# BBB_I2S_CAPE.net
KiCad netlist of a schematic drawn in EAGLE
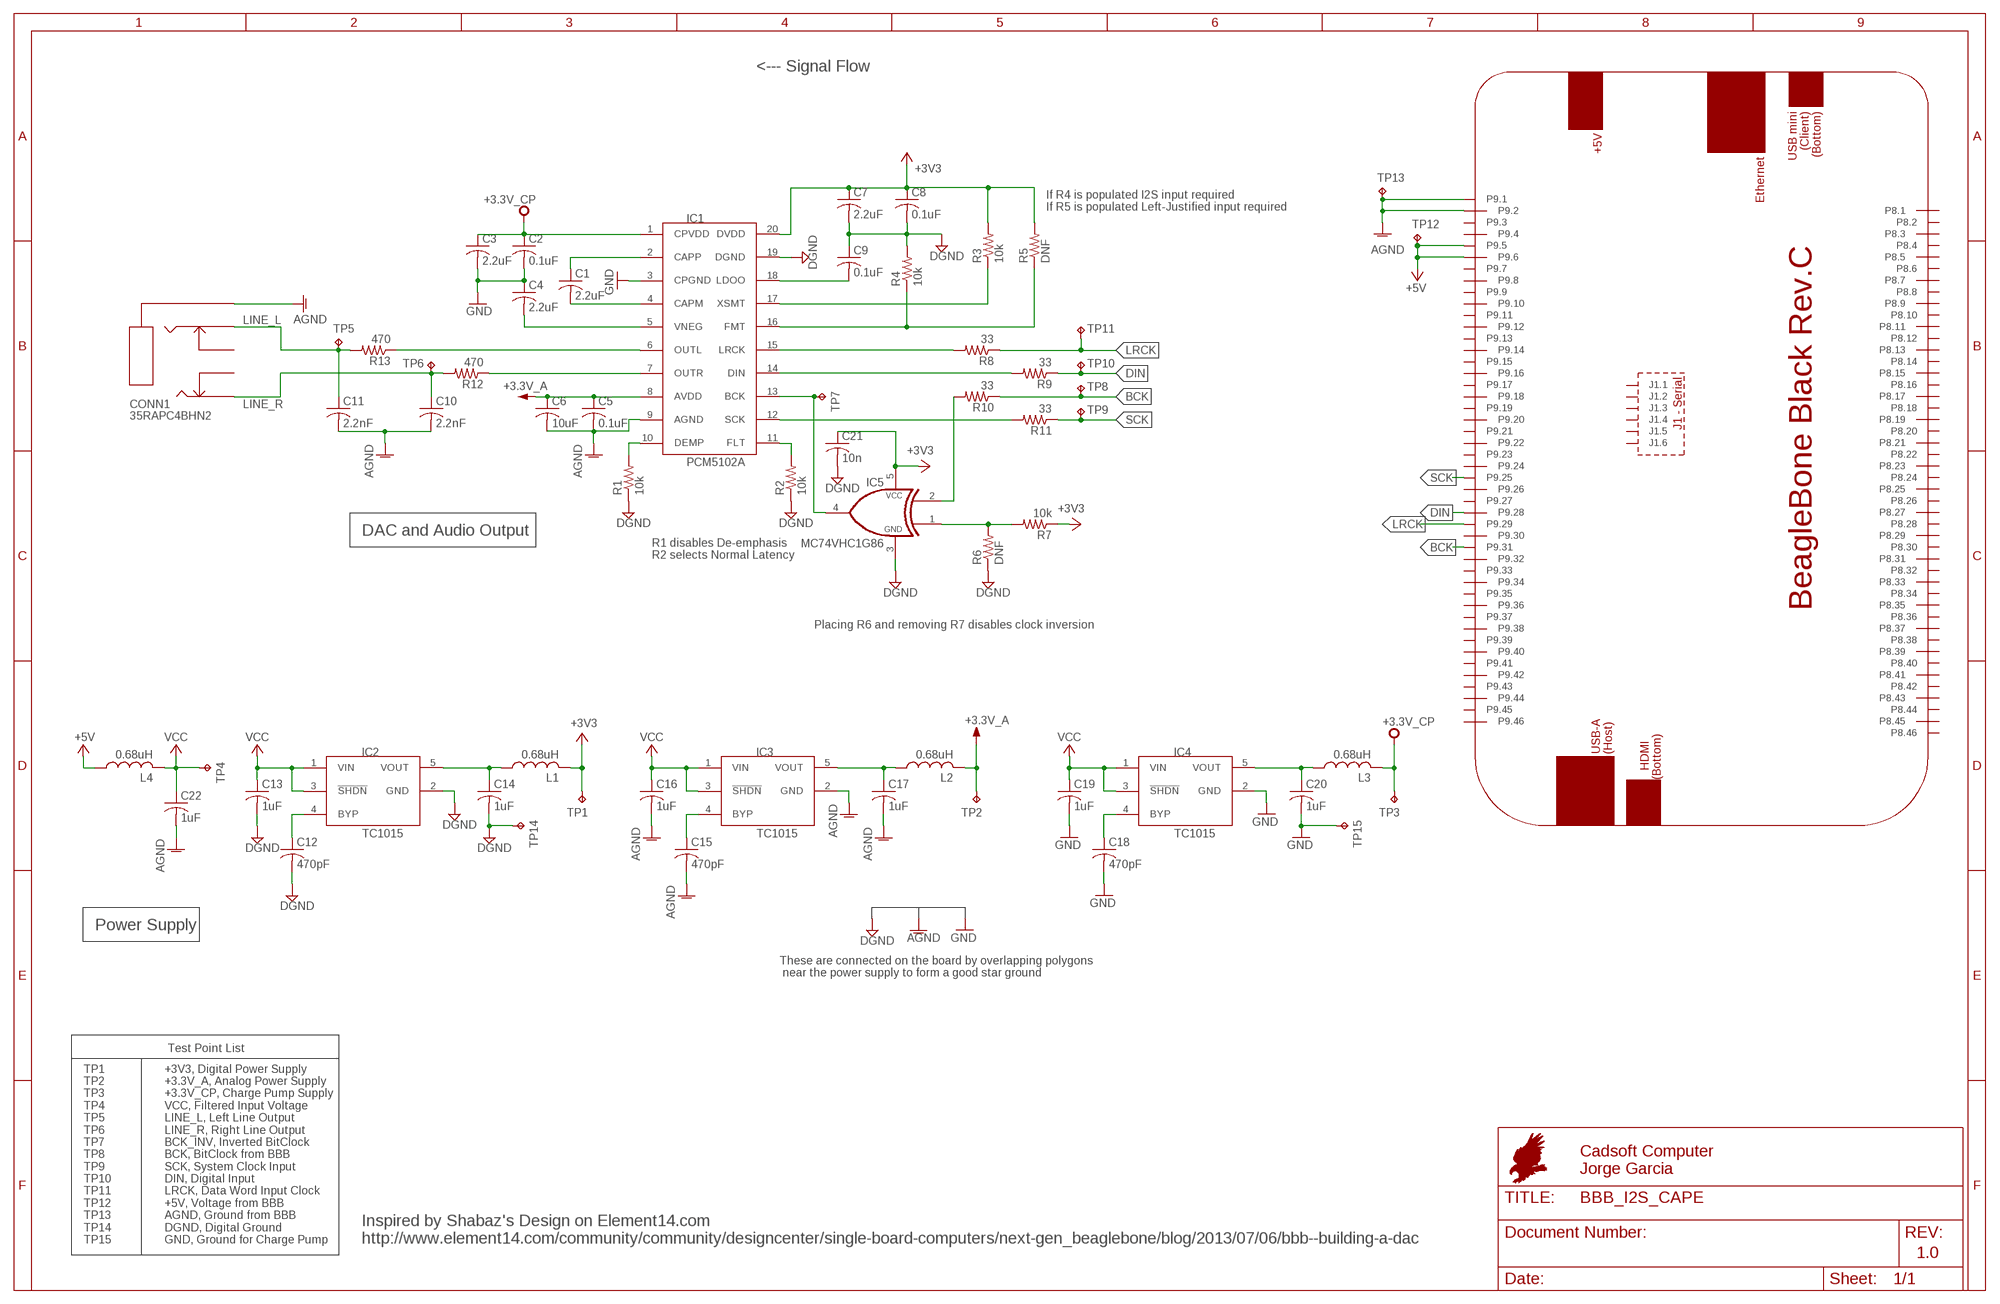
[diagram p0: schematic, sheet 1]

(export (version "E")
  (design (tool "Eeschema 10.0.6"))
  (components
    (comp (ref "C1")
      (value "2.2uF")
      (footprint "eagle-import:C0805")
      (fields (field (name "MPN") "GCM21BR71C225KA64L"))
      (libsource (lib "eagle-import") (part "C-USC0805"))
    )
    (comp (ref "C2")
      (value "0.1uF")
      (footprint "eagle-import:C0805")
      (fields (field (name "MF") "VISHAY/VITRAMON") (field (name "MPN") "VJ0805Y104KXAMT"))
      (libsource (lib "eagle-import") (part "C-USC0805"))
    )
    (comp (ref "C3")
      (value "2.2uF")
      (footprint "eagle-import:C0805")
      (fields (field (name "MPN") "GCM21BR71C225KA64L"))
      (libsource (lib "eagle-import") (part "C-USC0805"))
    )
    (comp (ref "C4")
      (value "2.2uF")
      (footprint "eagle-import:C0805")
      (fields (field (name "MPN") "GCM21BR71C225KA64L"))
      (libsource (lib "eagle-import") (part "C-USC0805"))
    )
    (comp (ref "C5")
      (value "0.1uF")
      (footprint "eagle-import:C0805")
      (fields (field (name "MF") "VISHAY/VITRAMON") (field (name "MPN") "VJ0805Y104KXAMT"))
      (libsource (lib "eagle-import") (part "C-USC0805"))
    )
    (comp (ref "C6")
      (value "10uF")
      (footprint "eagle-import:C0805")
      (fields (field (name "MPN") "08053D106KAT2A"))
      (libsource (lib "eagle-import") (part "C-USC0805"))
    )
    (comp (ref "C7")
      (value "2.2uF")
      (footprint "eagle-import:C0805")
      (fields (field (name "MPN") "GCM21BR71C225KA64L"))
      (libsource (lib "eagle-import") (part "C-USC0805"))
    )
    (comp (ref "C8")
      (value "0.1uF")
      (footprint "eagle-import:C0805")
      (fields (field (name "MF") "VISHAY/VITRAMON") (field (name "MPN") "VJ0805Y104KXAMT"))
      (libsource (lib "eagle-import") (part "C-USC0805"))
    )
    (comp (ref "C9")
      (value "0.1uF")
      (footprint "eagle-import:C0805")
      (fields (field (name "MF") "VISHAY/VITRAMON") (field (name "MPN") "VJ0805Y104KXAMT"))
      (libsource (lib "eagle-import") (part "C-USC0805"))
    )
    (comp (ref "C10")
      (value "2.2nF")
      (footprint "eagle-import:C0805")
      (fields (field (name "MF") "AVX CORPORATION") (field (name "MPN") "08055C222KAT2A"))
      (libsource (lib "eagle-import") (part "C-USC0805"))
    )
    (comp (ref "C11")
      (value "2.2nF")
      (footprint "eagle-import:C0805")
      (fields (field (name "MF") "AVX CORPORATION") (field (name "MPN") "08055C222KAT2A"))
      (libsource (lib "eagle-import") (part "C-USC0805"))
    )
    (comp (ref "C12")
      (value "470pF")
      (footprint "eagle-import:C0805")
      (fields (field (name "MPN") "MC0805B471K500CT"))
      (libsource (lib "eagle-import") (part "C-USC0805"))
    )
    (comp (ref "C13")
      (value "1uF")
      (footprint "eagle-import:C0805")
      (fields (field (name "MPN") "C0805X105K3RACAUTO"))
      (libsource (lib "eagle-import") (part "C-USC0805"))
    )
    (comp (ref "C14")
      (value "1uF")
      (footprint "eagle-import:C0805")
      (fields (field (name "MPN") "C0805X105K3RACAUTO"))
      (libsource (lib "eagle-import") (part "C-USC0805"))
    )
    (comp (ref "C15")
      (value "470pF")
      (footprint "eagle-import:C0805")
      (fields (field (name "MPN") "MC0805B471K500CT"))
      (libsource (lib "eagle-import") (part "C-USC0805"))
    )
    (comp (ref "C16")
      (value "1uF")
      (footprint "eagle-import:C0805")
      (fields (field (name "MPN") "C0805X105K3RACAUTO"))
      (libsource (lib "eagle-import") (part "C-USC0805"))
    )
    (comp (ref "C17")
      (value "1uF")
      (footprint "eagle-import:C0805")
      (fields (field (name "MPN") "C0805X105K3RACAUTO"))
      (libsource (lib "eagle-import") (part "C-USC0805"))
    )
    (comp (ref "C18")
      (value "470pF")
      (footprint "eagle-import:C0805")
      (fields (field (name "MPN") "MC0805B471K500CT"))
      (libsource (lib "eagle-import") (part "C-USC0805"))
    )
    (comp (ref "C19")
      (value "1uF")
      (footprint "eagle-import:C0805")
      (fields (field (name "MPN") "C0805X105K3RACAUTO"))
      (libsource (lib "eagle-import") (part "C-USC0805"))
    )
    (comp (ref "C20")
      (value "1uF")
      (footprint "eagle-import:C0805")
      (fields (field (name "MPN") "C0805X105K3RACAUTO"))
      (libsource (lib "eagle-import") (part "C-USC0805"))
    )
    (comp (ref "C21")
      (value "10n")
      (footprint "eagle-import:C0805")
      (fields (field (name "MPN") "MC0805B103K500CT"))
      (libsource (lib "eagle-import") (part "C-USC0805"))
    )
    (comp (ref "C22")
      (value "1uF")
      (footprint "eagle-import:C0805")
      (fields (field (name "MPN") "C0805X105K3RACAUTO"))
      (libsource (lib "eagle-import") (part "C-USC0805"))
    )
    (comp (ref "CONN1")
      (value "35RAPC4BHN2")
      (footprint "eagle-import:35RAPC4BHN2")
      (fields (field (name "MF") "SWITCHCRAFT"))
      (libsource (lib "eagle-import") (part "35RAPC4BHN2"))
    )
    (comp (ref "IC1")
      (value "PCM5102A")
      (footprint "eagle-import:TSSOP20")
      (fields (field (name "MPN") "PCM5102AQPWRQ1"))
      (libsource (lib "eagle-import") (part "PCM5102A"))
    )
    (comp (ref "IC2")
      (value "TC1015")
      (footprint "eagle-import:SOT23-5L")
      (fields (field (name "MPN") "TC1015-3.3VCT713"))
      (libsource (lib "eagle-import") (part "TC1015"))
    )
    (comp (ref "IC3")
      (value "TC1015")
      (footprint "eagle-import:SOT23-5L")
      (fields (field (name "MPN") "TC1015-3.3VCT713"))
      (libsource (lib "eagle-import") (part "TC1015"))
    )
    (comp (ref "IC4")
      (value "TC1015")
      (footprint "eagle-import:SOT23-5L")
      (fields (field (name "MPN") "TC1015-3.3VCT713"))
      (libsource (lib "eagle-import") (part "TC1015"))
    )
    (comp (ref "IC5")
      (value "MC74VHC1G86")
      (footprint "eagle-import:SOT23-5L")
      (fields (field (name "MF") "TEXAS INSTRUMENTS") (field (name "MPN") "SN74AHC1G86DBVR"))
      (libsource (lib "eagle-import") (part "MC74VHC1G86"))
    )
    (comp (ref "L1")
      (value "0.68uH")
      (footprint "eagle-import:R0805")
      (fields (field (name "MPN") "MCFT000156"))
      (libsource (lib "eagle-import") (part "INDUCTOR"))
    )
    (comp (ref "L2")
      (value "0.68uH")
      (footprint "eagle-import:R0805")
      (fields (field (name "MPN") "MCFT000156"))
      (libsource (lib "eagle-import") (part "INDUCTOR"))
    )
    (comp (ref "L3")
      (value "0.68uH")
      (footprint "eagle-import:R0805")
      (fields (field (name "MPN") "MCFT000156"))
      (libsource (lib "eagle-import") (part "INDUCTOR"))
    )
    (comp (ref "L4")
      (value "0.68uH")
      (footprint "eagle-import:R0805")
      (fields (field (name "MPN") "MCFT000156"))
      (libsource (lib "eagle-import") (part "INDUCTOR"))
    )
    (comp (ref "PCB1")
      (value "BEAGLEBONE_BLACK_CAPE")
      (footprint "eagle-import:BEAGLEBONE_BLACK_CAPE")
      (libsource (lib "eagle-import") (part "BEAGLEBONE_BLACK_CAPE"))
    )
    (comp (ref "R1")
      (value "10k")
      (footprint "eagle-import:R0805")
      (fields (field (name "MPN") "MCTC0525B1002T5E"))
      (libsource (lib "eagle-import") (part "R-US_R0805"))
    )
    (comp (ref "R2")
      (value "10k")
      (footprint "eagle-import:R0805")
      (fields (field (name "MPN") "MCTC0525B1002T5E"))
      (libsource (lib "eagle-import") (part "R-US_R0805"))
    )
    (comp (ref "R3")
      (value "10k")
      (footprint "eagle-import:R0805")
      (fields (field (name "MPN") "MCTC0525B1002T5E"))
      (libsource (lib "eagle-import") (part "R-US_R0805"))
    )
    (comp (ref "R4")
      (value "10k")
      (footprint "eagle-import:R0805")
      (fields (field (name "MPN") "MCTC0525B1002T5E"))
      (libsource (lib "eagle-import") (part "R-US_R0805"))
    )
    (comp (ref "R5")
      (value "DNF")
      (footprint "eagle-import:R0805")
      (libsource (lib "eagle-import") (part "R-US_R0805"))
    )
    (comp (ref "R6")
      (value "DNF")
      (footprint "eagle-import:R0805")
      (libsource (lib "eagle-import") (part "R-US_R0805"))
    )
    (comp (ref "R7")
      (value "10k")
      (footprint "eagle-import:R0805")
      (fields (field (name "MPN") "MCTC0525B1002T5E"))
      (libsource (lib "eagle-import") (part "R-US_R0805"))
    )
    (comp (ref "R8")
      (value "33")
      (footprint "eagle-import:R0805")
      (fields (field (name "MPN") "CR0805-JW-330ELF"))
      (libsource (lib "eagle-import") (part "R-US_R0805"))
    )
    (comp (ref "R9")
      (value "33")
      (footprint "eagle-import:R0805")
      (fields (field (name "MPN") "CR0805-JW-330ELF"))
      (libsource (lib "eagle-import") (part "R-US_R0805"))
    )
    (comp (ref "R10")
      (value "33")
      (footprint "eagle-import:R0805")
      (fields (field (name "MPN") "CR0805-JW-330ELF"))
      (libsource (lib "eagle-import") (part "R-US_R0805"))
    )
    (comp (ref "R11")
      (value "33")
      (footprint "eagle-import:R0805")
      (fields (field (name "MPN") "CR0805-JW-330ELF"))
      (libsource (lib "eagle-import") (part "R-US_R0805"))
    )
    (comp (ref "R12")
      (value "470")
      (footprint "eagle-import:R0805")
      (fields (field (name "MPN") "ERA-6AEB471V"))
      (libsource (lib "eagle-import") (part "R-US_R0805"))
    )
    (comp (ref "R13")
      (value "470")
      (footprint "eagle-import:R0805")
      (fields (field (name "MPN") "ERA-6AEB471V"))
      (libsource (lib "eagle-import") (part "R-US_R0805"))
    )
    (comp (ref "TP1")
      (value "TPPAD1-17")
      (footprint "eagle-import:P1-17")
      (libsource (lib "eagle-import") (part "TPPAD1-17"))
    )
    (comp (ref "TP2")
      (value "TPPAD1-17")
      (footprint "eagle-import:P1-17")
      (libsource (lib "eagle-import") (part "TPPAD1-17"))
    )
    (comp (ref "TP3")
      (value "TPPAD1-17")
      (footprint "eagle-import:P1-17")
      (libsource (lib "eagle-import") (part "TPPAD1-17"))
    )
    (comp (ref "TP4")
      (value "TPPAD1-17")
      (footprint "eagle-import:P1-17")
      (libsource (lib "eagle-import") (part "TPPAD1-17"))
    )
    (comp (ref "TP5")
      (value "TPPAD1-17")
      (footprint "eagle-import:P1-17")
      (libsource (lib "eagle-import") (part "TPPAD1-17"))
    )
    (comp (ref "TP6")
      (value "TPPAD1-17")
      (footprint "eagle-import:P1-17")
      (libsource (lib "eagle-import") (part "TPPAD1-17"))
    )
    (comp (ref "TP7")
      (value "TPPAD1-17")
      (footprint "eagle-import:P1-17")
      (libsource (lib "eagle-import") (part "TPPAD1-17"))
    )
    (comp (ref "TP8")
      (value "TPPAD1-17")
      (footprint "eagle-import:P1-17")
      (libsource (lib "eagle-import") (part "TPPAD1-17"))
    )
    (comp (ref "TP9")
      (value "TPPAD1-17")
      (footprint "eagle-import:P1-17")
      (libsource (lib "eagle-import") (part "TPPAD1-17"))
    )
    (comp (ref "TP10")
      (value "TPPAD1-17")
      (footprint "eagle-import:P1-17")
      (libsource (lib "eagle-import") (part "TPPAD1-17"))
    )
    (comp (ref "TP11")
      (value "TPPAD1-17")
      (footprint "eagle-import:P1-17")
      (libsource (lib "eagle-import") (part "TPPAD1-17"))
    )
    (comp (ref "TP12")
      (value "TPPAD1-17")
      (footprint "eagle-import:P1-17")
      (libsource (lib "eagle-import") (part "TPPAD1-17"))
    )
    (comp (ref "TP13")
      (value "TPPAD1-17")
      (footprint "eagle-import:P1-17")
      (libsource (lib "eagle-import") (part "TPPAD1-17"))
    )
    (comp (ref "TP14")
      (value "TPPAD1-17")
      (footprint "eagle-import:P1-17")
      (libsource (lib "eagle-import") (part "TPPAD1-17"))
    )
    (comp (ref "TP15")
      (value "TPPAD1-17")
      (footprint "eagle-import:P1-17")
      (libsource (lib "eagle-import") (part "TPPAD1-17"))
    )
  )
  (nets
    (net (code "1") (name "+3.3V_A") (class "Default")
      (node (ref "C5") (pin "1") (pinfunction "1_1") (pintype "passive"))
      (node (ref "C6") (pin "1") (pinfunction "1_1") (pintype "passive"))
      (node (ref "IC1") (pin "8") (pinfunction "AVDD_8") (pintype "bidirectional"))
      (node (ref "L2") (pin "2") (pinfunction "2_2") (pintype "passive"))
      (node (ref "TP2") (pin "TP") (pinfunction "TP_TP") (pintype "input"))
    )
    (net (code "2") (name "+3.3V_CP") (class "Default")
      (node (ref "C2") (pin "1") (pinfunction "1_1") (pintype "passive"))
      (node (ref "C3") (pin "1") (pinfunction "1_1") (pintype "passive"))
      (node (ref "IC1") (pin "1") (pinfunction "CPVDD_1") (pintype "bidirectional"))
      (node (ref "L3") (pin "2") (pinfunction "2_2") (pintype "passive"))
      (node (ref "TP3") (pin "TP") (pinfunction "TP_TP") (pintype "input"))
    )
    (net (code "3") (name "+3V3") (class "Default")
      (node (ref "C21") (pin "1") (pinfunction "1_1") (pintype "passive"))
      (node (ref "C7") (pin "1") (pinfunction "1_1") (pintype "passive"))
      (node (ref "C8") (pin "1") (pinfunction "1_1") (pintype "passive"))
      (node (ref "IC1") (pin "20") (pinfunction "DVDD_20") (pintype "bidirectional"))
      (node (ref "IC5") (pin "5") (pinfunction "VCC_5") (pintype "power_in"))
      (node (ref "L1") (pin "2") (pinfunction "2_2") (pintype "passive"))
      (node (ref "R3") (pin "2") (pinfunction "2_2") (pintype "passive"))
      (node (ref "R5") (pin "2") (pinfunction "2_2") (pintype "passive"))
      (node (ref "R7") (pin "1") (pinfunction "1_1") (pintype "passive"))
      (node (ref "TP1") (pin "TP") (pinfunction "TP_TP") (pintype "input"))
    )
    (net (code "4") (name "+5V") (class "Default")
      (node (ref "L4") (pin "1") (pinfunction "1_1") (pintype "passive"))
      (node (ref "PCB1") (pin "P9.5") (pinfunction "P9.5_P9.5") (pintype "bidirectional"))
      (node (ref "PCB1") (pin "P9.6") (pinfunction "P9.6_P9.6") (pintype "bidirectional"))
      (node (ref "TP12") (pin "TP") (pinfunction "TP_TP") (pintype "input"))
    )
    (net (code "5") (name "/LINE_L") (class "Default")
      (node (ref "C11") (pin "1") (pinfunction "1_1") (pintype "passive"))
      (node (ref "CONN1") (pin "3") (pinfunction "3_3") (pintype "bidirectional"))
      (node (ref "R13") (pin "2") (pinfunction "2_2") (pintype "passive"))
      (node (ref "TP5") (pin "TP") (pinfunction "TP_TP") (pintype "input"))
    )
    (net (code "6") (name "/LINE_R") (class "Default")
      (node (ref "C10") (pin "1") (pinfunction "1_1") (pintype "passive"))
      (node (ref "CONN1") (pin "2") (pinfunction "2_2") (pintype "bidirectional"))
      (node (ref "R12") (pin "2") (pinfunction "2_2") (pintype "passive"))
      (node (ref "TP6") (pin "TP") (pinfunction "TP_TP") (pintype "input"))
    )
    (net (code "7") (name "AGND") (class "Default")
      (node (ref "C10") (pin "2") (pinfunction "2_2") (pintype "passive"))
      (node (ref "C11") (pin "2") (pinfunction "2_2") (pintype "passive"))
      (node (ref "C15") (pin "2") (pinfunction "2_2") (pintype "passive"))
      (node (ref "C16") (pin "2") (pinfunction "2_2") (pintype "passive"))
      (node (ref "C17") (pin "2") (pinfunction "2_2") (pintype "passive"))
      (node (ref "C22") (pin "2") (pinfunction "2_2") (pintype "passive"))
      (node (ref "C5") (pin "2") (pinfunction "2_2") (pintype "passive"))
      (node (ref "C6") (pin "2") (pinfunction "2_2") (pintype "passive"))
      (node (ref "CONN1") (pin "1") (pinfunction "1_1") (pintype "bidirectional"))
      (node (ref "IC1") (pin "9") (pinfunction "AGND_9") (pintype "bidirectional"))
      (node (ref "IC3") (pin "2") (pinfunction "GND_2") (pintype "bidirectional"))
      (node (ref "PCB1") (pin "P9.1") (pinfunction "P9.1_P9.1") (pintype "bidirectional"))
      (node (ref "PCB1") (pin "P9.2") (pinfunction "P9.2_P9.2") (pintype "bidirectional"))
      (node (ref "TP13") (pin "TP") (pinfunction "TP_TP") (pintype "input"))
    )
    (net (code "8") (name "BCK") (class "Default")
      (node (ref "PCB1") (pin "P9.31") (pinfunction "P9.31_P9.31") (pintype "bidirectional"))
      (node (ref "R10") (pin "1") (pinfunction "1_1") (pintype "passive"))
      (node (ref "TP8") (pin "TP") (pinfunction "TP_TP") (pintype "input"))
    )
    (net (code "9") (name "DGND") (class "Default")
      (node (ref "C12") (pin "2") (pinfunction "2_2") (pintype "passive"))
      (node (ref "C13") (pin "2") (pinfunction "2_2") (pintype "passive"))
      (node (ref "C14") (pin "2") (pinfunction "2_2") (pintype "passive"))
      (node (ref "C21") (pin "2") (pinfunction "2_2") (pintype "passive"))
      (node (ref "C7") (pin "2") (pinfunction "2_2") (pintype "passive"))
      (node (ref "C8") (pin "2") (pinfunction "2_2") (pintype "passive"))
      (node (ref "C9") (pin "1") (pinfunction "1_1") (pintype "passive"))
      (node (ref "IC1") (pin "19") (pinfunction "DGND_19") (pintype "bidirectional"))
      (node (ref "IC2") (pin "2") (pinfunction "GND_2") (pintype "bidirectional"))
      (node (ref "IC5") (pin "3") (pinfunction "GND_3") (pintype "power_in"))
      (node (ref "R1") (pin "1") (pinfunction "1_1") (pintype "passive"))
      (node (ref "R2") (pin "1") (pinfunction "1_1") (pintype "passive"))
      (node (ref "R4") (pin "2") (pinfunction "2_2") (pintype "passive"))
      (node (ref "R6") (pin "1") (pinfunction "1_1") (pintype "passive"))
      (node (ref "TP14") (pin "TP") (pinfunction "TP_TP") (pintype "input"))
    )
    (net (code "10") (name "DIN") (class "Default")
      (node (ref "PCB1") (pin "P9.28") (pinfunction "P9.28_P9.28") (pintype "bidirectional"))
      (node (ref "R9") (pin "1") (pinfunction "1_1") (pintype "passive"))
      (node (ref "TP10") (pin "TP") (pinfunction "TP_TP") (pintype "input"))
    )
    (net (code "11") (name "GND") (class "Default")
      (node (ref "C18") (pin "2") (pinfunction "2_2") (pintype "passive"))
      (node (ref "C19") (pin "2") (pinfunction "2_2") (pintype "passive"))
      (node (ref "C2") (pin "2") (pinfunction "2_2") (pintype "passive"))
      (node (ref "C20") (pin "2") (pinfunction "2_2") (pintype "passive"))
      (node (ref "C3") (pin "2") (pinfunction "2_2") (pintype "passive"))
      (node (ref "C4") (pin "1") (pinfunction "1_1") (pintype "passive"))
      (node (ref "IC1") (pin "3") (pinfunction "CPGND_3") (pintype "bidirectional"))
      (node (ref "IC4") (pin "2") (pinfunction "GND_2") (pintype "bidirectional"))
      (node (ref "TP15") (pin "TP") (pinfunction "TP_TP") (pintype "input"))
    )
    (net (code "12") (name "LRCK") (class "Default")
      (node (ref "PCB1") (pin "P9.29") (pinfunction "P9.29_P9.29") (pintype "bidirectional"))
      (node (ref "R8") (pin "1") (pinfunction "1_1") (pintype "passive"))
      (node (ref "TP11") (pin "TP") (pinfunction "TP_TP") (pintype "input"))
    )
    (net (code "13") (name "Net-(IC1-BCK)") (class "Default")
      (node (ref "IC1") (pin "13") (pinfunction "BCK_13") (pintype "bidirectional"))
      (node (ref "IC5") (pin "4") (pinfunction "OUT_4") (pintype "output"))
      (node (ref "TP7") (pin "TP") (pinfunction "TP_TP") (pintype "input"))
    )
    (net (code "14") (name "Net-(IC1-CAPM)") (class "Default")
      (node (ref "C1") (pin "2") (pinfunction "2_2") (pintype "passive"))
      (node (ref "IC1") (pin "4") (pinfunction "CAPM_4") (pintype "bidirectional"))
    )
    (net (code "15") (name "Net-(IC1-CAPP)") (class "Default")
      (node (ref "C1") (pin "1") (pinfunction "1_1") (pintype "passive"))
      (node (ref "IC1") (pin "2") (pinfunction "CAPP_2") (pintype "bidirectional"))
    )
    (net (code "16") (name "Net-(IC1-DEMP)") (class "Default")
      (node (ref "IC1") (pin "10") (pinfunction "DEMP_10") (pintype "bidirectional"))
      (node (ref "R1") (pin "2") (pinfunction "2_2") (pintype "passive"))
    )
    (net (code "17") (name "Net-(IC1-DIN)") (class "Default")
      (node (ref "IC1") (pin "14") (pinfunction "DIN_14") (pintype "bidirectional"))
      (node (ref "R9") (pin "2") (pinfunction "2_2") (pintype "passive"))
    )
    (net (code "18") (name "Net-(IC1-FLT)") (class "Default")
      (node (ref "IC1") (pin "11") (pinfunction "FLT_11") (pintype "bidirectional"))
      (node (ref "R2") (pin "2") (pinfunction "2_2") (pintype "passive"))
    )
    (net (code "19") (name "Net-(IC1-FMT)") (class "Default")
      (node (ref "IC1") (pin "16") (pinfunction "FMT_16") (pintype "bidirectional"))
      (node (ref "R4") (pin "1") (pinfunction "1_1") (pintype "passive"))
      (node (ref "R5") (pin "1") (pinfunction "1_1") (pintype "passive"))
    )
    (net (code "20") (name "Net-(IC1-LDOO)") (class "Default")
      (node (ref "C9") (pin "2") (pinfunction "2_2") (pintype "passive"))
      (node (ref "IC1") (pin "18") (pinfunction "LDOO_18") (pintype "bidirectional"))
    )
    (net (code "21") (name "Net-(IC1-LRCK)") (class "Default")
      (node (ref "IC1") (pin "15") (pinfunction "LRCK_15") (pintype "bidirectional"))
      (node (ref "R8") (pin "2") (pinfunction "2_2") (pintype "passive"))
    )
    (net (code "22") (name "Net-(IC1-OUTL)") (class "Default")
      (node (ref "IC1") (pin "6") (pinfunction "OUTL_6") (pintype "bidirectional"))
      (node (ref "R13") (pin "1") (pinfunction "1_1") (pintype "passive"))
    )
    (net (code "23") (name "Net-(IC1-OUTR)") (class "Default")
      (node (ref "IC1") (pin "7") (pinfunction "OUTR_7") (pintype "bidirectional"))
      (node (ref "R12") (pin "1") (pinfunction "1_1") (pintype "passive"))
    )
    (net (code "24") (name "Net-(IC1-SCK)") (class "Default")
      (node (ref "IC1") (pin "12") (pinfunction "SCK_12") (pintype "bidirectional"))
      (node (ref "R11") (pin "2") (pinfunction "2_2") (pintype "passive"))
    )
    (net (code "25") (name "Net-(IC1-VNEG)") (class "Default")
      (node (ref "C4") (pin "2") (pinfunction "2_2") (pintype "passive"))
      (node (ref "IC1") (pin "5") (pinfunction "VNEG_5") (pintype "bidirectional"))
    )
    (net (code "26") (name "Net-(IC1-XSMT)") (class "Default")
      (node (ref "IC1") (pin "17") (pinfunction "XSMT_17") (pintype "bidirectional"))
      (node (ref "R3") (pin "1") (pinfunction "1_1") (pintype "passive"))
    )
    (net (code "27") (name "Net-(IC2-BYP)") (class "Default")
      (node (ref "C12") (pin "1") (pinfunction "1_1") (pintype "passive"))
      (node (ref "IC2") (pin "4") (pinfunction "BYP_4") (pintype "bidirectional"))
    )
    (net (code "28") (name "Net-(IC2-VOUT)") (class "Default")
      (node (ref "C14") (pin "1") (pinfunction "1_1") (pintype "passive"))
      (node (ref "IC2") (pin "5") (pinfunction "VOUT_5") (pintype "bidirectional"))
      (node (ref "L1") (pin "1") (pinfunction "1_1") (pintype "passive"))
    )
    (net (code "29") (name "Net-(IC3-BYP)") (class "Default")
      (node (ref "C15") (pin "1") (pinfunction "1_1") (pintype "passive"))
      (node (ref "IC3") (pin "4") (pinfunction "BYP_4") (pintype "bidirectional"))
    )
    (net (code "30") (name "Net-(IC3-VOUT)") (class "Default")
      (node (ref "C17") (pin "1") (pinfunction "1_1") (pintype "passive"))
      (node (ref "IC3") (pin "5") (pinfunction "VOUT_5") (pintype "bidirectional"))
      (node (ref "L2") (pin "1") (pinfunction "1_1") (pintype "passive"))
    )
    (net (code "31") (name "Net-(IC4-BYP)") (class "Default")
      (node (ref "C18") (pin "1") (pinfunction "1_1") (pintype "passive"))
      (node (ref "IC4") (pin "4") (pinfunction "BYP_4") (pintype "bidirectional"))
    )
    (net (code "32") (name "Net-(IC4-VOUT)") (class "Default")
      (node (ref "C20") (pin "1") (pinfunction "1_1") (pintype "passive"))
      (node (ref "IC4") (pin "5") (pinfunction "VOUT_5") (pintype "bidirectional"))
      (node (ref "L3") (pin "1") (pinfunction "1_1") (pintype "passive"))
    )
    (net (code "33") (name "Net-(IC5-INA)") (class "Default")
      (node (ref "IC5") (pin "2") (pinfunction "INA_2") (pintype "input"))
      (node (ref "R10") (pin "2") (pinfunction "2_2") (pintype "passive"))
    )
    (net (code "34") (name "Net-(IC5-INB)") (class "Default")
      (node (ref "IC5") (pin "1") (pinfunction "INB_1") (pintype "input"))
      (node (ref "R6") (pin "2") (pinfunction "2_2") (pintype "passive"))
      (node (ref "R7") (pin "2") (pinfunction "2_2") (pintype "passive"))
    )
    (net (code "35") (name "SCK") (class "Default")
      (node (ref "PCB1") (pin "P9.25") (pinfunction "P9.25_P9.25") (pintype "bidirectional"))
      (node (ref "R11") (pin "1") (pinfunction "1_1") (pintype "passive"))
      (node (ref "TP9") (pin "TP") (pinfunction "TP_TP") (pintype "input"))
    )
    (net (code "36") (name "VCC") (class "Default")
      (node (ref "C13") (pin "1") (pinfunction "1_1") (pintype "passive"))
      (node (ref "C16") (pin "1") (pinfunction "1_1") (pintype "passive"))
      (node (ref "C19") (pin "1") (pinfunction "1_1") (pintype "passive"))
      (node (ref "C22") (pin "1") (pinfunction "1_1") (pintype "passive"))
      (node (ref "IC2") (pin "1") (pinfunction "VIN_1") (pintype "bidirectional"))
      (node (ref "IC2") (pin "3") (pinfunction "~{SHDN}_3") (pintype "bidirectional"))
      (node (ref "IC3") (pin "1") (pinfunction "VIN_1") (pintype "bidirectional"))
      (node (ref "IC3") (pin "3") (pinfunction "~{SHDN}_3") (pintype "bidirectional"))
      (node (ref "IC4") (pin "1") (pinfunction "VIN_1") (pintype "bidirectional"))
      (node (ref "IC4") (pin "3") (pinfunction "~{SHDN}_3") (pintype "bidirectional"))
      (node (ref "L4") (pin "2") (pinfunction "2_2") (pintype "passive"))
      (node (ref "TP4") (pin "TP") (pinfunction "TP_TP") (pintype "input"))
    )
    (net (code "37") (name "unconnected-(CONN1-Pad10)") (class "Default")
      (node (ref "CONN1") (pin "10") (pinfunction "10_10") (pintype "bidirectional"))
    )
    (net (code "38") (name "unconnected-(CONN1-Pad11)") (class "Default")
      (node (ref "CONN1") (pin "11") (pinfunction "11_11") (pintype "bidirectional"))
    )
    (net (code "39") (name "unconnected-(PCB1-PadJ1.1)") (class "Default")
      (node (ref "PCB1") (pin "J1.1") (pinfunction "J1.1_J1.1") (pintype "bidirectional"))
    )
    (net (code "40") (name "unconnected-(PCB1-PadJ1.2)") (class "Default")
      (node (ref "PCB1") (pin "J1.2") (pinfunction "J1.2_J1.2") (pintype "bidirectional"))
    )
    (net (code "41") (name "unconnected-(PCB1-PadJ1.3)") (class "Default")
      (node (ref "PCB1") (pin "J1.3") (pinfunction "J1.3_J1.3") (pintype "bidirectional"))
    )
    (net (code "42") (name "unconnected-(PCB1-PadJ1.4)") (class "Default")
      (node (ref "PCB1") (pin "J1.4") (pinfunction "J1.4_J1.4") (pintype "bidirectional"))
    )
    (net (code "43") (name "unconnected-(PCB1-PadJ1.5)") (class "Default")
      (node (ref "PCB1") (pin "J1.5") (pinfunction "J1.5_J1.5") (pintype "bidirectional"))
    )
    (net (code "44") (name "unconnected-(PCB1-PadJ1.6)") (class "Default")
      (node (ref "PCB1") (pin "J1.6") (pinfunction "J1.6_J1.6") (pintype "bidirectional"))
    )
    (net (code "45") (name "unconnected-(PCB1-PadP8.1)") (class "Default")
      (node (ref "PCB1") (pin "P8.1") (pinfunction "P8.1_P8.1") (pintype "bidirectional"))
    )
    (net (code "46") (name "unconnected-(PCB1-PadP8.2)") (class "Default")
      (node (ref "PCB1") (pin "P8.2") (pinfunction "P8.2_P8.2") (pintype "bidirectional"))
    )
    (net (code "47") (name "unconnected-(PCB1-PadP8.3)") (class "Default")
      (node (ref "PCB1") (pin "P8.3") (pinfunction "P8.3_P8.3") (pintype "bidirectional"))
    )
    (net (code "48") (name "unconnected-(PCB1-PadP8.4)") (class "Default")
      (node (ref "PCB1") (pin "P8.4") (pinfunction "P8.4_P8.4") (pintype "bidirectional"))
    )
    (net (code "49") (name "unconnected-(PCB1-PadP8.5)") (class "Default")
      (node (ref "PCB1") (pin "P8.5") (pinfunction "P8.5_P8.5") (pintype "bidirectional"))
    )
    (net (code "50") (name "unconnected-(PCB1-PadP8.6)") (class "Default")
      (node (ref "PCB1") (pin "P8.6") (pinfunction "P8.6_P8.6") (pintype "bidirectional"))
    )
    (net (code "51") (name "unconnected-(PCB1-PadP8.7)") (class "Default")
      (node (ref "PCB1") (pin "P8.7") (pinfunction "P8.7_P8.7") (pintype "bidirectional"))
    )
    (net (code "52") (name "unconnected-(PCB1-PadP8.8)") (class "Default")
      (node (ref "PCB1") (pin "P8.8") (pinfunction "P8.8_P8.8") (pintype "bidirectional"))
    )
    (net (code "53") (name "unconnected-(PCB1-PadP8.9)") (class "Default")
      (node (ref "PCB1") (pin "P8.9") (pinfunction "P8.9_P8.9") (pintype "bidirectional"))
    )
    (net (code "54") (name "unconnected-(PCB1-PadP8.10)") (class "Default")
      (node (ref "PCB1") (pin "P8.10") (pinfunction "P8.10_P8.10") (pintype "bidirectional"))
    )
    (net (code "55") (name "unconnected-(PCB1-PadP8.11)") (class "Default")
      (node (ref "PCB1") (pin "P8.11") (pinfunction "P8.11_P8.11") (pintype "bidirectional"))
    )
    (net (code "56") (name "unconnected-(PCB1-PadP8.12)") (class "Default")
      (node (ref "PCB1") (pin "P8.12") (pinfunction "P8.12_P8.12") (pintype "bidirectional"))
    )
    (net (code "57") (name "unconnected-(PCB1-PadP8.13)") (class "Default")
      (node (ref "PCB1") (pin "P8.13") (pinfunction "P8.13_P8.13") (pintype "bidirectional"))
    )
    (net (code "58") (name "unconnected-(PCB1-PadP8.14)") (class "Default")
      (node (ref "PCB1") (pin "P8.14") (pinfunction "P8.14_P8.14") (pintype "bidirectional"))
    )
    (net (code "59") (name "unconnected-(PCB1-PadP8.15)") (class "Default")
      (node (ref "PCB1") (pin "P8.15") (pinfunction "P8.15_P8.15") (pintype "bidirectional"))
    )
    (net (code "60") (name "unconnected-(PCB1-PadP8.16)") (class "Default")
      (node (ref "PCB1") (pin "P8.16") (pinfunction "P8.16_P8.16") (pintype "bidirectional"))
    )
    (net (code "61") (name "unconnected-(PCB1-PadP8.17)") (class "Default")
      (node (ref "PCB1") (pin "P8.17") (pinfunction "P8.17_P8.17") (pintype "bidirectional"))
    )
    (net (code "62") (name "unconnected-(PCB1-PadP8.18)") (class "Default")
      (node (ref "PCB1") (pin "P8.18") (pinfunction "P8.18_P8.18") (pintype "bidirectional"))
    )
    (net (code "63") (name "unconnected-(PCB1-PadP8.19)") (class "Default")
      (node (ref "PCB1") (pin "P8.19") (pinfunction "P8.19_P8.19") (pintype "bidirectional"))
    )
    (net (code "64") (name "unconnected-(PCB1-PadP8.20)") (class "Default")
      (node (ref "PCB1") (pin "P8.20") (pinfunction "P8.20_P8.20") (pintype "bidirectional"))
    )
    (net (code "65") (name "unconnected-(PCB1-PadP8.21)") (class "Default")
      (node (ref "PCB1") (pin "P8.21") (pinfunction "P8.21_P8.21") (pintype "bidirectional"))
    )
    (net (code "66") (name "unconnected-(PCB1-PadP8.22)") (class "Default")
      (node (ref "PCB1") (pin "P8.22") (pinfunction "P8.22_P8.22") (pintype "bidirectional"))
    )
    (net (code "67") (name "unconnected-(PCB1-PadP8.23)") (class "Default")
      (node (ref "PCB1") (pin "P8.23") (pinfunction "P8.23_P8.23") (pintype "bidirectional"))
    )
    (net (code "68") (name "unconnected-(PCB1-PadP8.24)") (class "Default")
      (node (ref "PCB1") (pin "P8.24") (pinfunction "P8.24_P8.24") (pintype "bidirectional"))
    )
    (net (code "69") (name "unconnected-(PCB1-PadP8.25)") (class "Default")
      (node (ref "PCB1") (pin "P8.25") (pinfunction "P8.25_P8.25") (pintype "bidirectional"))
    )
    (net (code "70") (name "unconnected-(PCB1-PadP8.26)") (class "Default")
      (node (ref "PCB1") (pin "P8.26") (pinfunction "P8.26_P8.26") (pintype "bidirectional"))
    )
    (net (code "71") (name "unconnected-(PCB1-PadP8.27)") (class "Default")
      (node (ref "PCB1") (pin "P8.27") (pinfunction "P8.27_P8.27") (pintype "bidirectional"))
    )
    (net (code "72") (name "unconnected-(PCB1-PadP8.28)") (class "Default")
      (node (ref "PCB1") (pin "P8.28") (pinfunction "P8.28_P8.28") (pintype "bidirectional"))
    )
    (net (code "73") (name "unconnected-(PCB1-PadP8.29)") (class "Default")
      (node (ref "PCB1") (pin "P8.29") (pinfunction "P8.29_P8.29") (pintype "bidirectional"))
    )
    (net (code "74") (name "unconnected-(PCB1-PadP8.30)") (class "Default")
      (node (ref "PCB1") (pin "P8.30") (pinfunction "P8.30_P8.30") (pintype "bidirectional"))
    )
    (net (code "75") (name "unconnected-(PCB1-PadP8.31)") (class "Default")
      (node (ref "PCB1") (pin "P8.31") (pinfunction "P8.31_P8.31") (pintype "bidirectional"))
    )
    (net (code "76") (name "unconnected-(PCB1-PadP8.32)") (class "Default")
      (node (ref "PCB1") (pin "P8.32") (pinfunction "P8.32_P8.32") (pintype "bidirectional"))
    )
    (net (code "77") (name "unconnected-(PCB1-PadP8.33)") (class "Default")
      (node (ref "PCB1") (pin "P8.33") (pinfunction "P8.33_P8.33") (pintype "bidirectional"))
    )
    (net (code "78") (name "unconnected-(PCB1-PadP8.34)") (class "Default")
      (node (ref "PCB1") (pin "P8.34") (pinfunction "P8.34_P8.34") (pintype "bidirectional"))
    )
    (net (code "79") (name "unconnected-(PCB1-PadP8.35)") (class "Default")
      (node (ref "PCB1") (pin "P8.35") (pinfunction "P8.35_P8.35") (pintype "bidirectional"))
    )
    (net (code "80") (name "unconnected-(PCB1-PadP8.36)") (class "Default")
      (node (ref "PCB1") (pin "P8.36") (pinfunction "P8.36_P8.36") (pintype "bidirectional"))
    )
    (net (code "81") (name "unconnected-(PCB1-PadP8.37)") (class "Default")
      (node (ref "PCB1") (pin "P8.37") (pinfunction "P8.37_P8.37") (pintype "bidirectional"))
    )
    (net (code "82") (name "unconnected-(PCB1-PadP8.38)") (class "Default")
      (node (ref "PCB1") (pin "P8.38") (pinfunction "P8.38_P8.38") (pintype "bidirectional"))
    )
    (net (code "83") (name "unconnected-(PCB1-PadP8.39)") (class "Default")
      (node (ref "PCB1") (pin "P8.39") (pinfunction "P8.39_P8.39") (pintype "bidirectional"))
    )
    (net (code "84") (name "unconnected-(PCB1-PadP8.40)") (class "Default")
      (node (ref "PCB1") (pin "P8.40") (pinfunction "P8.40_P8.40") (pintype "bidirectional"))
    )
    (net (code "85") (name "unconnected-(PCB1-PadP8.41)") (class "Default")
      (node (ref "PCB1") (pin "P8.41") (pinfunction "P8.41_P8.41") (pintype "bidirectional"))
    )
    (net (code "86") (name "unconnected-(PCB1-PadP8.42)") (class "Default")
      (node (ref "PCB1") (pin "P8.42") (pinfunction "P8.42_P8.42") (pintype "bidirectional"))
    )
    (net (code "87") (name "unconnected-(PCB1-PadP8.43)") (class "Default")
      (node (ref "PCB1") (pin "P8.43") (pinfunction "P8.43_P8.43") (pintype "bidirectional"))
    )
    (net (code "88") (name "unconnected-(PCB1-PadP8.44)") (class "Default")
      (node (ref "PCB1") (pin "P8.44") (pinfunction "P8.44_P8.44") (pintype "bidirectional"))
    )
    (net (code "89") (name "unconnected-(PCB1-PadP8.45)") (class "Default")
      (node (ref "PCB1") (pin "P8.45") (pinfunction "P8.45_P8.45") (pintype "bidirectional"))
    )
    (net (code "90") (name "unconnected-(PCB1-PadP8.46)") (class "Default")
      (node (ref "PCB1") (pin "P8.46") (pinfunction "P8.46_P8.46") (pintype "bidirectional"))
    )
    (net (code "91") (name "unconnected-(PCB1-PadP9.3)") (class "Default")
      (node (ref "PCB1") (pin "P9.3") (pinfunction "P9.3_P9.3") (pintype "bidirectional"))
    )
    (net (code "92") (name "unconnected-(PCB1-PadP9.4)") (class "Default")
      (node (ref "PCB1") (pin "P9.4") (pinfunction "P9.4_P9.4") (pintype "bidirectional"))
    )
    (net (code "93") (name "unconnected-(PCB1-PadP9.7)") (class "Default")
      (node (ref "PCB1") (pin "P9.7") (pinfunction "P9.7_P9.7") (pintype "bidirectional"))
    )
    (net (code "94") (name "unconnected-(PCB1-PadP9.8)") (class "Default")
      (node (ref "PCB1") (pin "P9.8") (pinfunction "P9.8_P9.8") (pintype "bidirectional"))
    )
    (net (code "95") (name "unconnected-(PCB1-PadP9.9)") (class "Default")
      (node (ref "PCB1") (pin "P9.9") (pinfunction "P9.9_P9.9") (pintype "bidirectional"))
    )
    (net (code "96") (name "unconnected-(PCB1-PadP9.10)") (class "Default")
      (node (ref "PCB1") (pin "P9.10") (pinfunction "P9.10_P9.10") (pintype "bidirectional"))
    )
    (net (code "97") (name "unconnected-(PCB1-PadP9.11)") (class "Default")
      (node (ref "PCB1") (pin "P9.11") (pinfunction "P9.11_P9.11") (pintype "bidirectional"))
    )
    (net (code "98") (name "unconnected-(PCB1-PadP9.12)") (class "Default")
      (node (ref "PCB1") (pin "P9.12") (pinfunction "P9.12_P9.12") (pintype "bidirectional"))
    )
    (net (code "99") (name "unconnected-(PCB1-PadP9.13)") (class "Default")
      (node (ref "PCB1") (pin "P9.13") (pinfunction "P9.13_P9.13") (pintype "bidirectional"))
    )
    (net (code "100") (name "unconnected-(PCB1-PadP9.14)") (class "Default")
      (node (ref "PCB1") (pin "P9.14") (pinfunction "P9.14_P9.14") (pintype "bidirectional"))
    )
    (net (code "101") (name "unconnected-(PCB1-PadP9.15)") (class "Default")
      (node (ref "PCB1") (pin "P9.15") (pinfunction "P9.15_P9.15") (pintype "bidirectional"))
    )
    (net (code "102") (name "unconnected-(PCB1-PadP9.16)") (class "Default")
      (node (ref "PCB1") (pin "P9.16") (pinfunction "P9.16_P9.16") (pintype "bidirectional"))
    )
    (net (code "103") (name "unconnected-(PCB1-PadP9.17)") (class "Default")
      (node (ref "PCB1") (pin "P9.17") (pinfunction "P9.17_P9.17") (pintype "bidirectional"))
    )
    (net (code "104") (name "unconnected-(PCB1-PadP9.18)") (class "Default")
      (node (ref "PCB1") (pin "P9.18") (pinfunction "P9.18_P9.18") (pintype "bidirectional"))
    )
    (net (code "105") (name "unconnected-(PCB1-PadP9.19)") (class "Default")
      (node (ref "PCB1") (pin "P9.19") (pinfunction "P9.19_P9.19") (pintype "bidirectional"))
    )
    (net (code "106") (name "unconnected-(PCB1-PadP9.20)") (class "Default")
      (node (ref "PCB1") (pin "P9.20") (pinfunction "P9.20_P9.20") (pintype "bidirectional"))
    )
    (net (code "107") (name "unconnected-(PCB1-PadP9.21)") (class "Default")
      (node (ref "PCB1") (pin "P9.21") (pinfunction "P9.21_P9.21") (pintype "bidirectional"))
    )
    (net (code "108") (name "unconnected-(PCB1-PadP9.22)") (class "Default")
      (node (ref "PCB1") (pin "P9.22") (pinfunction "P9.22_P9.22") (pintype "bidirectional"))
    )
    (net (code "109") (name "unconnected-(PCB1-PadP9.23)") (class "Default")
      (node (ref "PCB1") (pin "P9.23") (pinfunction "P9.23_P9.23") (pintype "bidirectional"))
    )
    (net (code "110") (name "unconnected-(PCB1-PadP9.24)") (class "Default")
      (node (ref "PCB1") (pin "P9.24") (pinfunction "P9.24_P9.24") (pintype "bidirectional"))
    )
    (net (code "111") (name "unconnected-(PCB1-PadP9.26)") (class "Default")
      (node (ref "PCB1") (pin "P9.26") (pinfunction "P9.26_P9.26") (pintype "bidirectional"))
    )
    (net (code "112") (name "unconnected-(PCB1-PadP9.27)") (class "Default")
      (node (ref "PCB1") (pin "P9.27") (pinfunction "P9.27_P9.27") (pintype "bidirectional"))
    )
    (net (code "113") (name "unconnected-(PCB1-PadP9.30)") (class "Default")
      (node (ref "PCB1") (pin "P9.30") (pinfunction "P9.30_P9.30") (pintype "bidirectional"))
    )
    (net (code "114") (name "unconnected-(PCB1-PadP9.32)") (class "Default")
      (node (ref "PCB1") (pin "P9.32") (pinfunction "P9.32_P9.32") (pintype "bidirectional"))
    )
    (net (code "115") (name "unconnected-(PCB1-PadP9.33)") (class "Default")
      (node (ref "PCB1") (pin "P9.33") (pinfunction "P9.33_P9.33") (pintype "bidirectional"))
    )
    (net (code "116") (name "unconnected-(PCB1-PadP9.34)") (class "Default")
      (node (ref "PCB1") (pin "P9.34") (pinfunction "P9.34_P9.34") (pintype "bidirectional"))
    )
    (net (code "117") (name "unconnected-(PCB1-PadP9.35)") (class "Default")
      (node (ref "PCB1") (pin "P9.35") (pinfunction "P9.35_P9.35") (pintype "bidirectional"))
    )
    (net (code "118") (name "unconnected-(PCB1-PadP9.36)") (class "Default")
      (node (ref "PCB1") (pin "P9.36") (pinfunction "P9.36_P9.36") (pintype "bidirectional"))
    )
    (net (code "119") (name "unconnected-(PCB1-PadP9.37)") (class "Default")
      (node (ref "PCB1") (pin "P9.37") (pinfunction "P9.37_P9.37") (pintype "bidirectional"))
    )
    (net (code "120") (name "unconnected-(PCB1-PadP9.38)") (class "Default")
      (node (ref "PCB1") (pin "P9.38") (pinfunction "P9.38_P9.38") (pintype "bidirectional"))
    )
    (net (code "121") (name "unconnected-(PCB1-PadP9.39)") (class "Default")
      (node (ref "PCB1") (pin "P9.39") (pinfunction "P9.39_P9.39") (pintype "bidirectional"))
    )
    (net (code "122") (name "unconnected-(PCB1-PadP9.40)") (class "Default")
      (node (ref "PCB1") (pin "P9.40") (pinfunction "P9.40_P9.40") (pintype "bidirectional"))
    )
    (net (code "123") (name "unconnected-(PCB1-PadP9.41)") (class "Default")
      (node (ref "PCB1") (pin "P9.41") (pinfunction "P9.41_P9.41") (pintype "bidirectional"))
    )
    (net (code "124") (name "unconnected-(PCB1-PadP9.42)") (class "Default")
      (node (ref "PCB1") (pin "P9.42") (pinfunction "P9.42_P9.42") (pintype "bidirectional"))
    )
    (net (code "125") (name "unconnected-(PCB1-PadP9.43)") (class "Default")
      (node (ref "PCB1") (pin "P9.43") (pinfunction "P9.43_P9.43") (pintype "bidirectional"))
    )
    (net (code "126") (name "unconnected-(PCB1-PadP9.44)") (class "Default")
      (node (ref "PCB1") (pin "P9.44") (pinfunction "P9.44_P9.44") (pintype "bidirectional"))
    )
    (net (code "127") (name "unconnected-(PCB1-PadP9.45)") (class "Default")
      (node (ref "PCB1") (pin "P9.45") (pinfunction "P9.45_P9.45") (pintype "bidirectional"))
    )
    (net (code "128") (name "unconnected-(PCB1-PadP9.46)") (class "Default")
      (node (ref "PCB1") (pin "P9.46") (pinfunction "P9.46_P9.46") (pintype "bidirectional"))
    )
  )
)
